# ROV_MainBoard_V2_0.net
KiCad netlist of a schematic drawn in Altium Designer
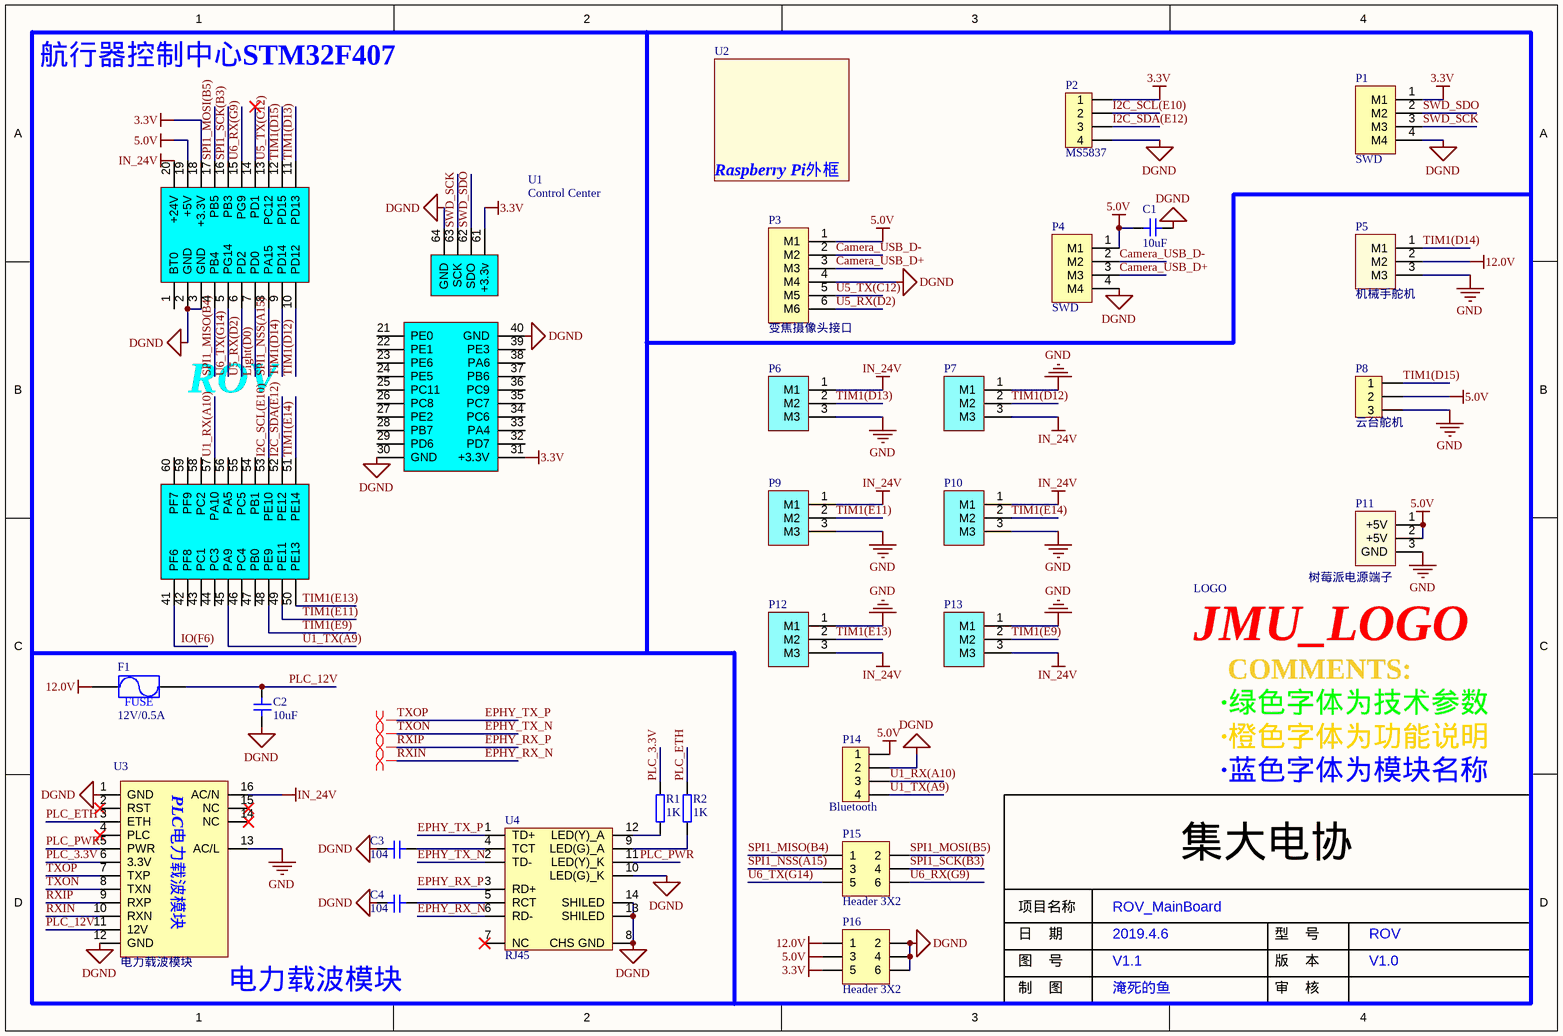
[diagram p0: ROV_MainBoard V2.0.SchDoc]

(export (version "E")
  (design (tool "Eeschema 10.0.6"))
  (components
    (comp (ref "C1")
      (value "10uF")
      (footprint "0805C")
      (description "无极贴片电容")
      (libsource (lib "集大电协1.2") (part "Cap1"))
    )
    (comp (ref "C2")
      (value "10uF")
      (footprint "1206C")
      (description "无极贴片电容")
      (libsource (lib "集大电协1.2") (part "Cap1"))
    )
    (comp (ref "C3")
      (value "104")
      (footprint "0805C")
      (description "无极贴片电容")
      (libsource (lib "集大电协1.1.2") (part "Cap1"))
    )
    (comp (ref "C4")
      (value "104")
      (footprint "0805C")
      (description "无极贴片电容")
      (libsource (lib "集大电协1.1.2") (part "Cap1"))
    )
    (comp (ref "F1")
      (value "12V/0.5A")
      (footprint "FUSE-1206")
      (description "保险丝")
      (libsource (lib "集大电协1.2") (part "Fuse"))
    )
    (comp (ref "LOGO")
      (value "~")
      (footprint "JMU_LOGO(1.35cm)")
      (description "LOGO")
      (libsource (lib "集大电协1.2") (part "JMU_LOGO"))
    )
    (comp (ref "P1")
      (value "SWD")
      (footprint "XH4/2.54mm/180")
      (description "4PIN")
      (libsource (lib "集大电协1.2") (part "接线端子-4PIN"))
    )
    (comp (ref "P2")
      (value "MS5837")
      (footprint "MX1.25-4PIN")
      (description "排针")
      (libsource (lib "集大电协1.2") (part "Header 4"))
    )
    (comp (ref "P3")
      (value "变焦摄像头接口")
      (footprint "XH6/2.54mm/180")
      (description "6PIN")
      (libsource (lib "集大电协1.2") (part "接线端子-6PIN"))
    )
    (comp (ref "P4")
      (value "SWD")
      (footprint "XH4/2.54mm/180")
      (description "4PIN")
      (libsource (lib "集大电协1.2") (part "接线端子-4PIN"))
    )
    (comp (ref "P5")
      (value "机械手舵机")
      (footprint "KF128-3P")
      (description "3PIN")
      (libsource (lib "集大电协1.2") (part "接线端子-3PIN"))
    )
    (comp (ref "P6")
      (value "~")
      (footprint "KF2EDGK5.0-3P")
      (description "3PIN")
      (libsource (lib "集大电协1.2") (part "接线端子-3PIN"))
    )
    (comp (ref "P7")
      (value "~")
      (footprint "KF2EDGK5.0-3P")
      (description "3PIN")
      (libsource (lib "集大电协1.2") (part "接线端子-3PIN"))
    )
    (comp (ref "P8")
      (value "云台舵机")
      (footprint "HEADER 3H")
      (description "排针")
      (libsource (lib "集大电协1.2") (part "Header 3"))
    )
    (comp (ref "P9")
      (value "~")
      (footprint "KF2EDGK5.0-3P")
      (description "3PIN")
      (libsource (lib "集大电协1.2") (part "接线端子-3PIN"))
    )
    (comp (ref "P10")
      (value "~")
      (footprint "KF2EDGK5.0-3P")
      (description "3PIN")
      (libsource (lib "集大电协1.2") (part "接线端子-3PIN"))
    )
    (comp (ref "P11")
      (value "树莓派电源端子")
      (footprint "XH3/2.54mm/180")
      (description "3PIN")
      (libsource (lib "") (part "接线端子-3PIN_1"))
    )
    (comp (ref "P12")
      (value "~")
      (footprint "KF2EDGK5.0-3P")
      (description "3PIN")
      (libsource (lib "集大电协1.2") (part "接线端子-3PIN"))
    )
    (comp (ref "P13")
      (value "~")
      (footprint "KF2EDGK5.0-3P")
      (description "3PIN")
      (libsource (lib "集大电协1.2") (part "接线端子-3PIN"))
    )
    (comp (ref "P14")
      (value "Bluetooth")
      (footprint "Header 4(排母)")
      (description "排针")
      (libsource (lib "集大电协1.2") (part "Header 4"))
    )
    (comp (ref "P15")
      (value "Header 3X2")
      (footprint "Header 3X2")
      (description "双排排针")
      (libsource (lib "集大电协1.2") (part "Header 3X2"))
    )
    (comp (ref "P16")
      (value "Header 3X2")
      (footprint "Header 3X2")
      (description "双排排针")
      (libsource (lib "集大电协1.2") (part "Header 3X2"))
    )
    (comp (ref "R1")
      (value "1K")
      (footprint "0805R")
      (description "电阻")
      (libsource (lib "集大电协1.2") (part "Res"))
    )
    (comp (ref "R2")
      (value "1K")
      (footprint "0805R")
      (description "电阻")
      (libsource (lib "集大电协1.2") (part "Res"))
    )
    (comp (ref "U1")
      (value "Control Center")
      (footprint "ROV_Control")
      (libsource (lib "集大电协1.2") (part "ROV_Controler"))
    )
    (comp (ref "U2")
      (value "~")
      (footprint "Raspberry Pi")
      (libsource (lib "集大电协1.2") (part "Raspberry Pi 外框"))
    )
    (comp (ref "U3")
      (value "电力载波模块")
      (footprint "电力载波模块6410")
      (libsource (lib "集大电协1.2") (part "电力载波模块6410"))
    )
    (comp (ref "U4") (value "RJ45") (footprint "RJ45") (libsource (lib "集大电协1.2") (part "RJ45")))
  )
  (nets
    (net (code "1") (name "/Camera_USB_D+") (class "Default")
      (node (ref "P3") (pin "3") (pinfunction "M3_3") (pintype "passive"))
      (node (ref "P4") (pin "3") (pinfunction "M3_3") (pintype "passive"))
    )
    (net (code "2") (name "/Camera_USB_D-") (class "Default")
      (node (ref "P3") (pin "2") (pinfunction "M2_2") (pintype "passive"))
      (node (ref "P4") (pin "2") (pinfunction "M2_2") (pintype "passive"))
    )
    (net (code "3") (name "/EPHY_RX_N") (class "Default")
      (node (ref "U3") (pin "10") (pinfunction "RXN_10") (pintype "passive"))
      (node (ref "U4") (pin "6") (pinfunction "RD-_6") (pintype "passive"))
    )
    (net (code "4") (name "/EPHY_RX_P") (class "Default")
      (node (ref "U3") (pin "9") (pinfunction "RXP_9") (pintype "passive"))
      (node (ref "U4") (pin "3") (pinfunction "RD+_3") (pintype "passive"))
    )
    (net (code "5") (name "/EPHY_TX_N") (class "Default")
      (node (ref "U3") (pin "8") (pinfunction "TXN_8") (pintype "passive"))
      (node (ref "U4") (pin "2") (pinfunction "TD-_2") (pintype "passive"))
    )
    (net (code "6") (name "/EPHY_TX_P") (class "Default")
      (node (ref "U3") (pin "7") (pinfunction "TXP_7") (pintype "passive"))
      (node (ref "U4") (pin "1") (pinfunction "TD+_1") (pintype "passive"))
    )
    (net (code "7") (name "/I2C_SCL(E10)") (class "Default")
      (node (ref "P2") (pin "2") (pinfunction "2_2") (pintype "passive"))
      (node (ref "U1") (pin "53") (pinfunction "PE10_53") (pintype "passive"))
    )
    (net (code "8") (name "/I2C_SDA(E12)") (class "Default")
      (node (ref "P2") (pin "3") (pinfunction "3_3") (pintype "passive"))
      (node (ref "U1") (pin "52") (pinfunction "PE12_52") (pintype "passive"))
    )
    (net (code "9") (name "/IO(F6)") (class "Default")
      (node (ref "U1") (pin "41") (pinfunction "PF6_41") (pintype "passive"))
    )
    (net (code "10") (name "/Light(D0)") (class "Default")
      (node (ref "U1") (pin "7") (pinfunction "PD0_7") (pintype "passive"))
    )
    (net (code "11") (name "/PLC_3.3V") (class "Default")
      (node (ref "R1") (pin "2") (pinfunction "2_2") (pintype "passive"))
      (node (ref "U3") (pin "6") (pinfunction "3.3V_6") (pintype "passive"))
    )
    (net (code "12") (name "/PLC_12V") (class "Default")
      (node (ref "C2") (pin "2") (pinfunction "2_2") (pintype "passive"))
      (node (ref "F1") (pin "2") (pinfunction "2_2") (pintype "passive"))
      (node (ref "U3") (pin "11") (pinfunction "12V_11") (pintype "passive"))
    )
    (net (code "13") (name "/PLC_ETH") (class "Default")
      (node (ref "R2") (pin "1") (pinfunction "1_1") (pintype "passive"))
      (node (ref "U3") (pin "3") (pinfunction "ETH_3") (pintype "passive"))
    )
    (net (code "14") (name "/PLC_PWR") (class "Default")
      (node (ref "U3") (pin "5") (pinfunction "PWR_5") (pintype "passive"))
      (node (ref "U4") (pin "11") (pinfunction "LED(Y)_K_11") (pintype "passive"))
    )
    (net (code "15") (name "/SPI1_MISO(B4)") (class "Default")
      (node (ref "P15") (pin "1") (pinfunction "1_1") (pintype "passive"))
      (node (ref "U1") (pin "4") (pinfunction "PB4_4") (pintype "passive"))
    )
    (net (code "16") (name "/SPI1_MOSI(B5)") (class "Default")
      (node (ref "P15") (pin "2") (pinfunction "2_2") (pintype "passive"))
      (node (ref "U1") (pin "17") (pinfunction "PB5_17") (pintype "passive"))
    )
    (net (code "17") (name "/SPI1_NSS(A15)") (class "Default")
      (node (ref "P15") (pin "3") (pinfunction "3_3") (pintype "passive"))
      (node (ref "U1") (pin "8") (pinfunction "PA15_8") (pintype "passive"))
    )
    (net (code "18") (name "/SPI1_SCK(B3)") (class "Default")
      (node (ref "P15") (pin "4") (pinfunction "4_4") (pintype "passive"))
      (node (ref "U1") (pin "16") (pinfunction "PB3_16") (pintype "passive"))
    )
    (net (code "19") (name "/SWD_SCK") (class "Default")
      (node (ref "P1") (pin "3") (pinfunction "M3_3") (pintype "passive"))
      (node (ref "U1") (pin "63") (pinfunction "SCK_63") (pintype "passive"))
    )
    (net (code "20") (name "/SWD_SDO") (class "Default")
      (node (ref "P1") (pin "2") (pinfunction "M2_2") (pintype "passive"))
      (node (ref "U1") (pin "62") (pinfunction "SDO_62") (pintype "passive"))
    )
    (net (code "21") (name "/TIM1(D12)") (class "Default")
      (node (ref "P7") (pin "2") (pinfunction "M2_2") (pintype "passive"))
      (node (ref "U1") (pin "10") (pinfunction "PD12_10") (pintype "passive"))
    )
    (net (code "22") (name "/TIM1(D13)") (class "Default")
      (node (ref "P6") (pin "2") (pinfunction "M2_2") (pintype "passive"))
      (node (ref "U1") (pin "11") (pinfunction "PD13_11") (pintype "passive"))
    )
    (net (code "23") (name "/TIM1(D14)") (class "Default")
      (node (ref "P5") (pin "1") (pinfunction "M1_1") (pintype "passive"))
      (node (ref "U1") (pin "9") (pinfunction "PD14_9") (pintype "passive"))
    )
    (net (code "24") (name "/TIM1(D15)") (class "Default")
      (node (ref "P8") (pin "1") (pinfunction "1_1") (pintype "passive"))
      (node (ref "U1") (pin "12") (pinfunction "PD15_12") (pintype "passive"))
    )
    (net (code "25") (name "/TIM1(E9)") (class "Default")
      (node (ref "P13") (pin "2") (pinfunction "M2_2") (pintype "passive"))
      (node (ref "U1") (pin "48") (pinfunction "PE9_48") (pintype "passive"))
    )
    (net (code "26") (name "/TIM1(E11)") (class "Default")
      (node (ref "P9") (pin "2") (pinfunction "M2_2") (pintype "passive"))
      (node (ref "U1") (pin "49") (pinfunction "PE11_49") (pintype "passive"))
    )
    (net (code "27") (name "/TIM1(E13)") (class "Default")
      (node (ref "P12") (pin "2") (pinfunction "M2_2") (pintype "passive"))
      (node (ref "U1") (pin "50") (pinfunction "PE13_50") (pintype "passive"))
    )
    (net (code "28") (name "/TIM1(E14)") (class "Default")
      (node (ref "P10") (pin "2") (pinfunction "M2_2") (pintype "passive"))
      (node (ref "U1") (pin "51") (pinfunction "PE14_51") (pintype "passive"))
    )
    (net (code "29") (name "/U1_RX(A10)") (class "Default")
      (node (ref "P14") (pin "3") (pinfunction "3_3") (pintype "passive"))
      (node (ref "U1") (pin "57") (pinfunction "PA10_57") (pintype "passive"))
    )
    (net (code "30") (name "/U1_TX(A9)") (class "Default")
      (node (ref "P14") (pin "4") (pinfunction "4_4") (pintype "passive"))
      (node (ref "U1") (pin "45") (pinfunction "PA9_45") (pintype "passive"))
    )
    (net (code "31") (name "/U5_RX(D2)") (class "Default")
      (node (ref "P3") (pin "6") (pinfunction "M6_6") (pintype "passive"))
      (node (ref "U1") (pin "6") (pinfunction "PD2_6") (pintype "passive"))
    )
    (net (code "32") (name "/U5_TX(C12)") (class "Default")
      (node (ref "P3") (pin "5") (pinfunction "M5_5") (pintype "passive"))
      (node (ref "U1") (pin "13") (pinfunction "PC12_13") (pintype "passive"))
    )
    (net (code "33") (name "/U6_RX(G9)") (class "Default")
      (node (ref "P15") (pin "6") (pinfunction "6_6") (pintype "passive"))
      (node (ref "U1") (pin "15") (pinfunction "PG9_15") (pintype "passive"))
    )
    (net (code "34") (name "/U6_TX(G14)") (class "Default")
      (node (ref "P15") (pin "5") (pinfunction "5_5") (pintype "passive"))
      (node (ref "U1") (pin "5") (pinfunction "PG14_5") (pintype "passive"))
    )
    (net (code "35") (name "3.3V") (class "Default")
      (node (ref "P1") (pin "1") (pinfunction "M1_1") (pintype "passive"))
      (node (ref "P16") (pin "5") (pinfunction "5_5") (pintype "passive"))
      (node (ref "P2") (pin "1") (pinfunction "1_1") (pintype "passive"))
      (node (ref "U1") (pin "18") (pinfunction "+3.3V_18") (pintype "passive"))
      (node (ref "U1") (pin "31") (pinfunction "+3.3V_31") (pintype "passive"))
      (node (ref "U1") (pin "61") (pinfunction "+3.3v_61") (pintype "passive"))
    )
    (net (code "36") (name "5.0V") (class "Default")
      (node (ref "C1") (pin "2") (pinfunction "2_2") (pintype "passive"))
      (node (ref "P11") (pin "1") (pinfunction "+5V_1") (pintype "passive"))
      (node (ref "P11") (pin "2") (pinfunction "+5V_2") (pintype "passive"))
      (node (ref "P14") (pin "1") (pinfunction "1_1") (pintype "passive"))
      (node (ref "P16") (pin "3") (pinfunction "3_3") (pintype "passive"))
      (node (ref "P3") (pin "1") (pinfunction "M1_1") (pintype "passive"))
      (node (ref "P4") (pin "1") (pinfunction "M1_1") (pintype "passive"))
      (node (ref "P8") (pin "2") (pinfunction "2_2") (pintype "passive"))
      (node (ref "U1") (pin "19") (pinfunction "+5V_19") (pintype "passive"))
    )
    (net (code "37") (name "12.0V") (class "Default")
      (node (ref "F1") (pin "1") (pinfunction "1_1") (pintype "passive"))
      (node (ref "P16") (pin "1") (pinfunction "1_1") (pintype "passive"))
      (node (ref "P5") (pin "2") (pinfunction "M2_2") (pintype "passive"))
    )
    (net (code "38") (name "DGND") (class "Default")
      (node (ref "C1") (pin "1") (pinfunction "1_1") (pintype "passive"))
      (node (ref "C2") (pin "1") (pinfunction "1_1") (pintype "passive"))
      (node (ref "C3") (pin "1") (pinfunction "1_1") (pintype "passive"))
      (node (ref "C4") (pin "1") (pinfunction "1_1") (pintype "passive"))
      (node (ref "P1") (pin "4") (pinfunction "M4_4") (pintype "passive"))
      (node (ref "P14") (pin "2") (pinfunction "2_2") (pintype "passive"))
      (node (ref "P16") (pin "2") (pinfunction "2_2") (pintype "passive"))
      (node (ref "P16") (pin "4") (pinfunction "4_4") (pintype "passive"))
      (node (ref "P16") (pin "6") (pinfunction "6_6") (pintype "passive"))
      (node (ref "P2") (pin "4") (pinfunction "4_4") (pintype "passive"))
      (node (ref "P3") (pin "4") (pinfunction "M4_4") (pintype "passive"))
      (node (ref "P4") (pin "4") (pinfunction "M4_4") (pintype "passive"))
      (node (ref "U1") (pin "2") (pinfunction "GND_2") (pintype "passive"))
      (node (ref "U1") (pin "3") (pinfunction "GND_3") (pintype "passive"))
      (node (ref "U1") (pin "30") (pinfunction "GND_30") (pintype "passive"))
      (node (ref "U1") (pin "40") (pinfunction "GND_40") (pintype "passive"))
      (node (ref "U1") (pin "64") (pinfunction "GND_64") (pintype "passive"))
      (node (ref "U3") (pin "1") (pinfunction "GND_1") (pintype "passive"))
      (node (ref "U3") (pin "12") (pinfunction "GND_12") (pintype "passive"))
      (node (ref "U4") (pin "10") (pinfunction "LED(G)_K_10") (pintype "passive"))
      (node (ref "U4") (pin "13") (pinfunction "SHILED_13") (pintype "passive"))
      (node (ref "U4") (pin "14") (pinfunction "SHILED_14") (pintype "passive"))
      (node (ref "U4") (pin "8") (pinfunction "CHS_GND_8") (pintype "passive"))
    )
    (net (code "39") (name "GND") (class "Default")
      (node (ref "P10") (pin "3") (pinfunction "M3_3") (pintype "passive"))
      (node (ref "P11") (pin "3") (pinfunction "GND_3") (pintype "passive"))
      (node (ref "P12") (pin "1") (pinfunction "M1_1") (pintype "passive"))
      (node (ref "P13") (pin "1") (pinfunction "M1_1") (pintype "passive"))
      (node (ref "P5") (pin "3") (pinfunction "M3_3") (pintype "passive"))
      (node (ref "P6") (pin "3") (pinfunction "M3_3") (pintype "passive"))
      (node (ref "P7") (pin "1") (pinfunction "M1_1") (pintype "passive"))
      (node (ref "P8") (pin "3") (pinfunction "3_3") (pintype "passive"))
      (node (ref "P9") (pin "3") (pinfunction "M3_3") (pintype "passive"))
      (node (ref "U3") (pin "13") (pinfunction "AC/L_13") (pintype "passive"))
    )
    (net (code "40") (name "IN_24V") (class "Default")
      (node (ref "P10") (pin "1") (pinfunction "M1_1") (pintype "passive"))
      (node (ref "P12") (pin "3") (pinfunction "M3_3") (pintype "passive"))
      (node (ref "P13") (pin "3") (pinfunction "M3_3") (pintype "passive"))
      (node (ref "P6") (pin "1") (pinfunction "M1_1") (pintype "passive"))
      (node (ref "P7") (pin "3") (pinfunction "M3_3") (pintype "passive"))
      (node (ref "P9") (pin "1") (pinfunction "M1_1") (pintype "passive"))
      (node (ref "U1") (pin "20") (pinfunction "+24V_20") (pintype "passive"))
      (node (ref "U3") (pin "16") (pinfunction "AC/N_16") (pintype "passive"))
    )
    (net (code "41") (name "Net-(U4-LED(G)_A)") (class "Default")
      (node (ref "R2") (pin "2") (pinfunction "2_2") (pintype "passive"))
      (node (ref "U4") (pin "9") (pinfunction "LED(G)_A_9") (pintype "passive"))
    )
    (net (code "42") (name "Net-(U4-LED(Y)_A)") (class "Default")
      (node (ref "R1") (pin "1") (pinfunction "1_1") (pintype "passive"))
      (node (ref "U4") (pin "12") (pinfunction "LED(Y)_A_12") (pintype "passive"))
    )
    (net (code "43") (name "Net-(U4-RCT)") (class "Default")
      (node (ref "C4") (pin "2") (pinfunction "2_2") (pintype "passive"))
      (node (ref "U4") (pin "5") (pinfunction "RCT_5") (pintype "passive"))
    )
    (net (code "44") (name "Net-(U4-TCT)") (class "Default")
      (node (ref "C3") (pin "2") (pinfunction "2_2") (pintype "passive"))
      (node (ref "U4") (pin "4") (pinfunction "TCT_4") (pintype "passive"))
    )
    (net (code "45") (name "unconnected-(U1-BT0-Pad1)") (class "Default")
      (node (ref "U1") (pin "1") (pinfunction "BT0_1") (pintype "passive"))
    )
    (net (code "46") (name "unconnected-(U1-PA4-Pad33)") (class "Default")
      (node (ref "U1") (pin "33") (pinfunction "PA4_33") (pintype "passive"))
    )
    (net (code "47") (name "unconnected-(U1-PA5-Pad56)") (class "Default")
      (node (ref "U1") (pin "56") (pinfunction "PA5_56") (pintype "passive"))
    )
    (net (code "48") (name "unconnected-(U1-PA6-Pad38)") (class "Default")
      (node (ref "U1") (pin "38") (pinfunction "PA6_38") (pintype "passive"))
    )
    (net (code "49") (name "unconnected-(U1-PB0-Pad47)") (class "Default")
      (node (ref "U1") (pin "47") (pinfunction "PB0_47") (pintype "passive"))
    )
    (net (code "50") (name "unconnected-(U1-PB1-Pad54)") (class "Default")
      (node (ref "U1") (pin "54") (pinfunction "PB1_54") (pintype "passive"))
    )
    (net (code "51") (name "unconnected-(U1-PB6-Pad37)") (class "Default")
      (node (ref "U1") (pin "37") (pinfunction "PB6_37") (pintype "passive"))
    )
    (net (code "52") (name "unconnected-(U1-PB7-Pad28)") (class "Default")
      (node (ref "U1") (pin "28") (pinfunction "PB7_28") (pintype "passive"))
    )
    (net (code "53") (name "unconnected-(U1-PC1-Pad43)") (class "Default")
      (node (ref "U1") (pin "43") (pinfunction "PC1_43") (pintype "passive"))
    )
    (net (code "54") (name "unconnected-(U1-PC2-Pad58)") (class "Default")
      (node (ref "U1") (pin "58") (pinfunction "PC2_58") (pintype "passive"))
    )
    (net (code "55") (name "unconnected-(U1-PC3-Pad44)") (class "Default")
      (node (ref "U1") (pin "44") (pinfunction "PC3_44") (pintype "passive"))
    )
    (net (code "56") (name "unconnected-(U1-PC4-Pad46)") (class "Default")
      (node (ref "U1") (pin "46") (pinfunction "PC4_46") (pintype "passive"))
    )
    (net (code "57") (name "unconnected-(U1-PC5-Pad55)") (class "Default")
      (node (ref "U1") (pin "55") (pinfunction "PC5_55") (pintype "passive"))
    )
    (net (code "58") (name "unconnected-(U1-PC6-Pad34)") (class "Default")
      (node (ref "U1") (pin "34") (pinfunction "PC6_34") (pintype "passive"))
    )
    (net (code "59") (name "unconnected-(U1-PC7-Pad35)") (class "Default")
      (node (ref "U1") (pin "35") (pinfunction "PC7_35") (pintype "passive"))
    )
    (net (code "60") (name "unconnected-(U1-PC8-Pad26)") (class "Default")
      (node (ref "U1") (pin "26") (pinfunction "PC8_26") (pintype "passive"))
    )
    (net (code "61") (name "unconnected-(U1-PC9-Pad36)") (class "Default")
      (node (ref "U1") (pin "36") (pinfunction "PC9_36") (pintype "passive"))
    )
    (net (code "62") (name "unconnected-(U1-PC11-Pad25)") (class "Default")
      (node (ref "U1") (pin "25") (pinfunction "PC11_25") (pintype "passive"))
    )
    (net (code "63") (name "unconnected-(U1-PD1-Pad14)") (class "Default")
      (node (ref "U1") (pin "14") (pinfunction "PD1_14") (pintype "passive+no_connect"))
    )
    (net (code "64") (name "unconnected-(U1-PD6-Pad29)") (class "Default")
      (node (ref "U1") (pin "29") (pinfunction "PD6_29") (pintype "passive"))
    )
    (net (code "65") (name "unconnected-(U1-PD7-Pad32)") (class "Default")
      (node (ref "U1") (pin "32") (pinfunction "PD7_32") (pintype "passive"))
    )
    (net (code "66") (name "unconnected-(U1-PE0-Pad21)") (class "Default")
      (node (ref "U1") (pin "21") (pinfunction "PE0_21") (pintype "passive"))
    )
    (net (code "67") (name "unconnected-(U1-PE1-Pad22)") (class "Default")
      (node (ref "U1") (pin "22") (pinfunction "PE1_22") (pintype "passive"))
    )
    (net (code "68") (name "unconnected-(U1-PE2-Pad27)") (class "Default")
      (node (ref "U1") (pin "27") (pinfunction "PE2_27") (pintype "passive"))
    )
    (net (code "69") (name "unconnected-(U1-PE3-Pad39)") (class "Default")
      (node (ref "U1") (pin "39") (pinfunction "PE3_39") (pintype "passive"))
    )
    (net (code "70") (name "unconnected-(U1-PE5-Pad24)") (class "Default")
      (node (ref "U1") (pin "24") (pinfunction "PE5_24") (pintype "passive"))
    )
    (net (code "71") (name "unconnected-(U1-PE6-Pad23)") (class "Default")
      (node (ref "U1") (pin "23") (pinfunction "PE6_23") (pintype "passive"))
    )
    (net (code "72") (name "unconnected-(U1-PF7-Pad60)") (class "Default")
      (node (ref "U1") (pin "60") (pinfunction "PF7_60") (pintype "passive"))
    )
    (net (code "73") (name "unconnected-(U1-PF8-Pad42)") (class "Default")
      (node (ref "U1") (pin "42") (pinfunction "PF8_42") (pintype "passive"))
    )
    (net (code "74") (name "unconnected-(U1-PF9-Pad59)") (class "Default")
      (node (ref "U1") (pin "59") (pinfunction "PF9_59") (pintype "passive"))
    )
    (net (code "75") (name "unconnected-(U3-NC-Pad14)") (class "Default")
      (node (ref "U3") (pin "14") (pinfunction "NC_14") (pintype "passive+no_connect"))
    )
    (net (code "76") (name "unconnected-(U3-NC-Pad15)") (class "Default")
      (node (ref "U3") (pin "15") (pinfunction "NC_15") (pintype "passive+no_connect"))
    )
    (net (code "77") (name "unconnected-(U3-PLC-Pad4)") (class "Default")
      (node (ref "U3") (pin "4") (pinfunction "PLC_4") (pintype "passive+no_connect"))
    )
    (net (code "78") (name "unconnected-(U3-RST-Pad2)") (class "Default")
      (node (ref "U3") (pin "2") (pinfunction "RST_2") (pintype "passive+no_connect"))
    )
    (net (code "79") (name "unconnected-(U4-NC-Pad7)") (class "Default")
      (node (ref "U4") (pin "7") (pinfunction "NC_7") (pintype "passive+no_connect"))
    )
  )
)
